# KGGR_wD_HK.net
KiCad netlist of a schematic drawn in EAGLE
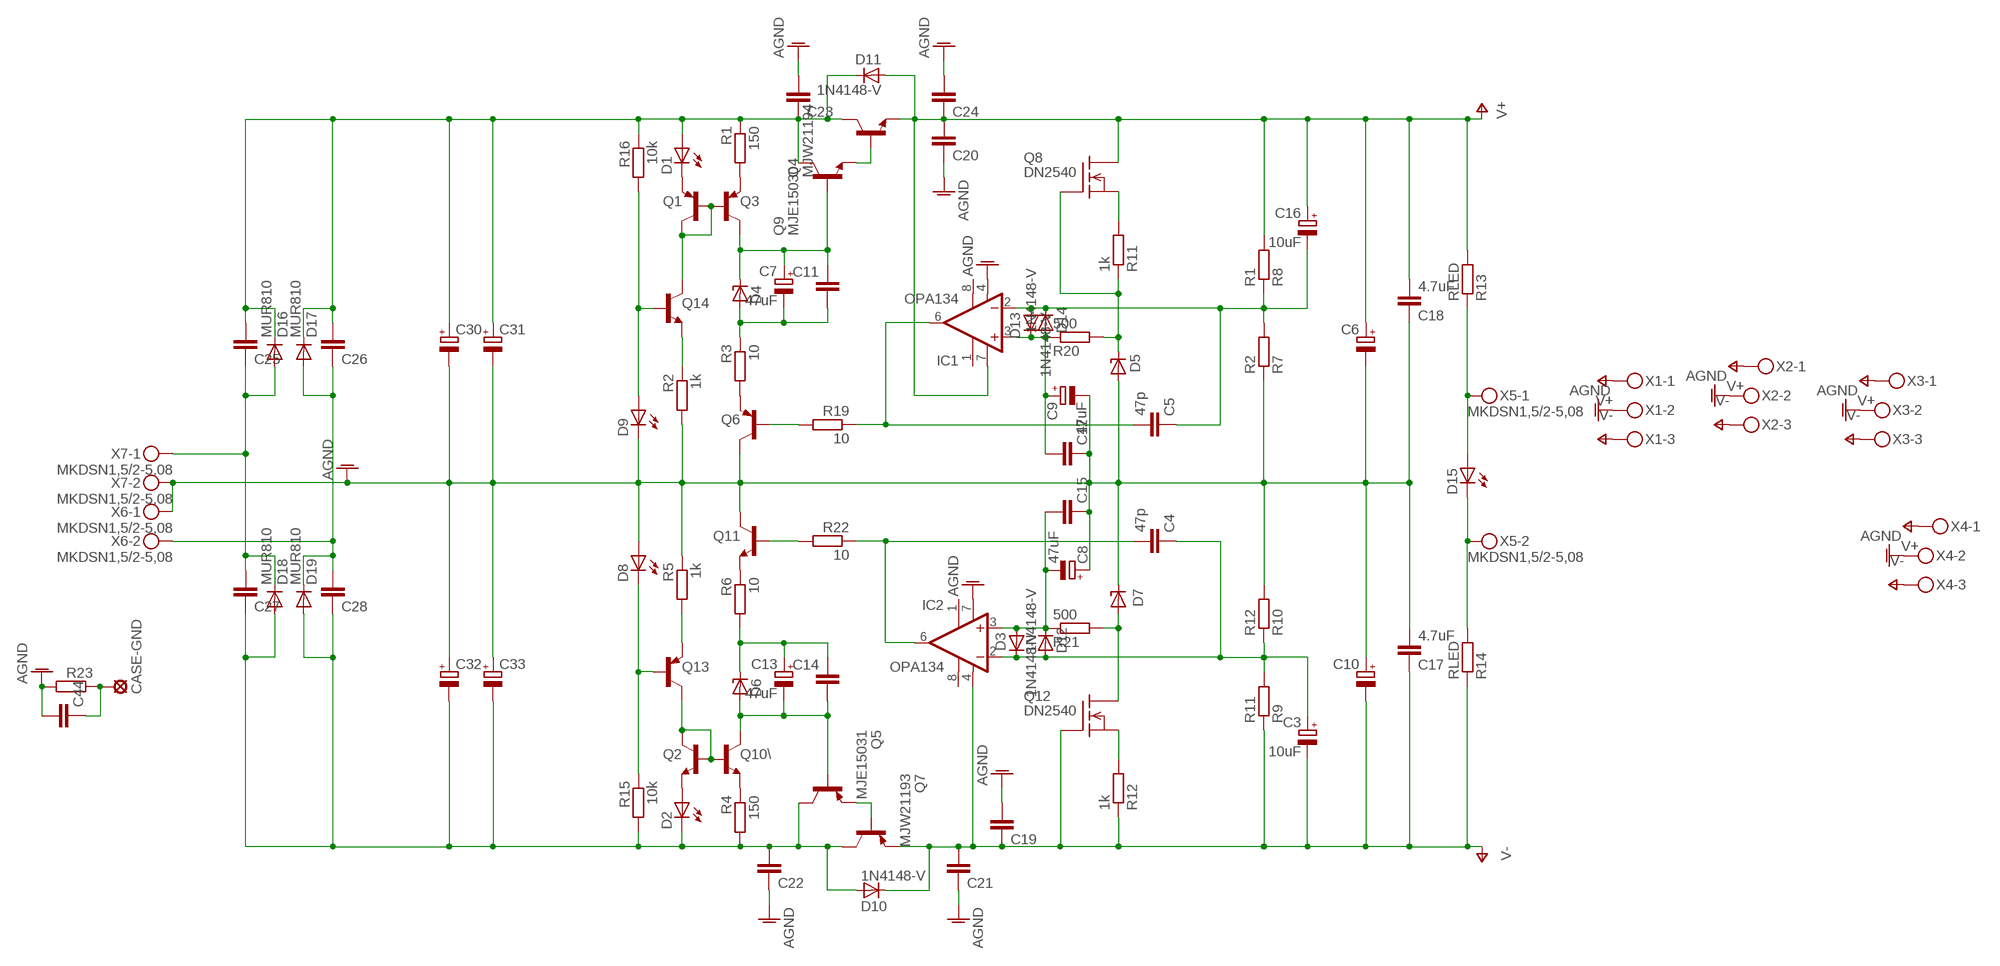
[diagram p0: schematic, sheet 1]
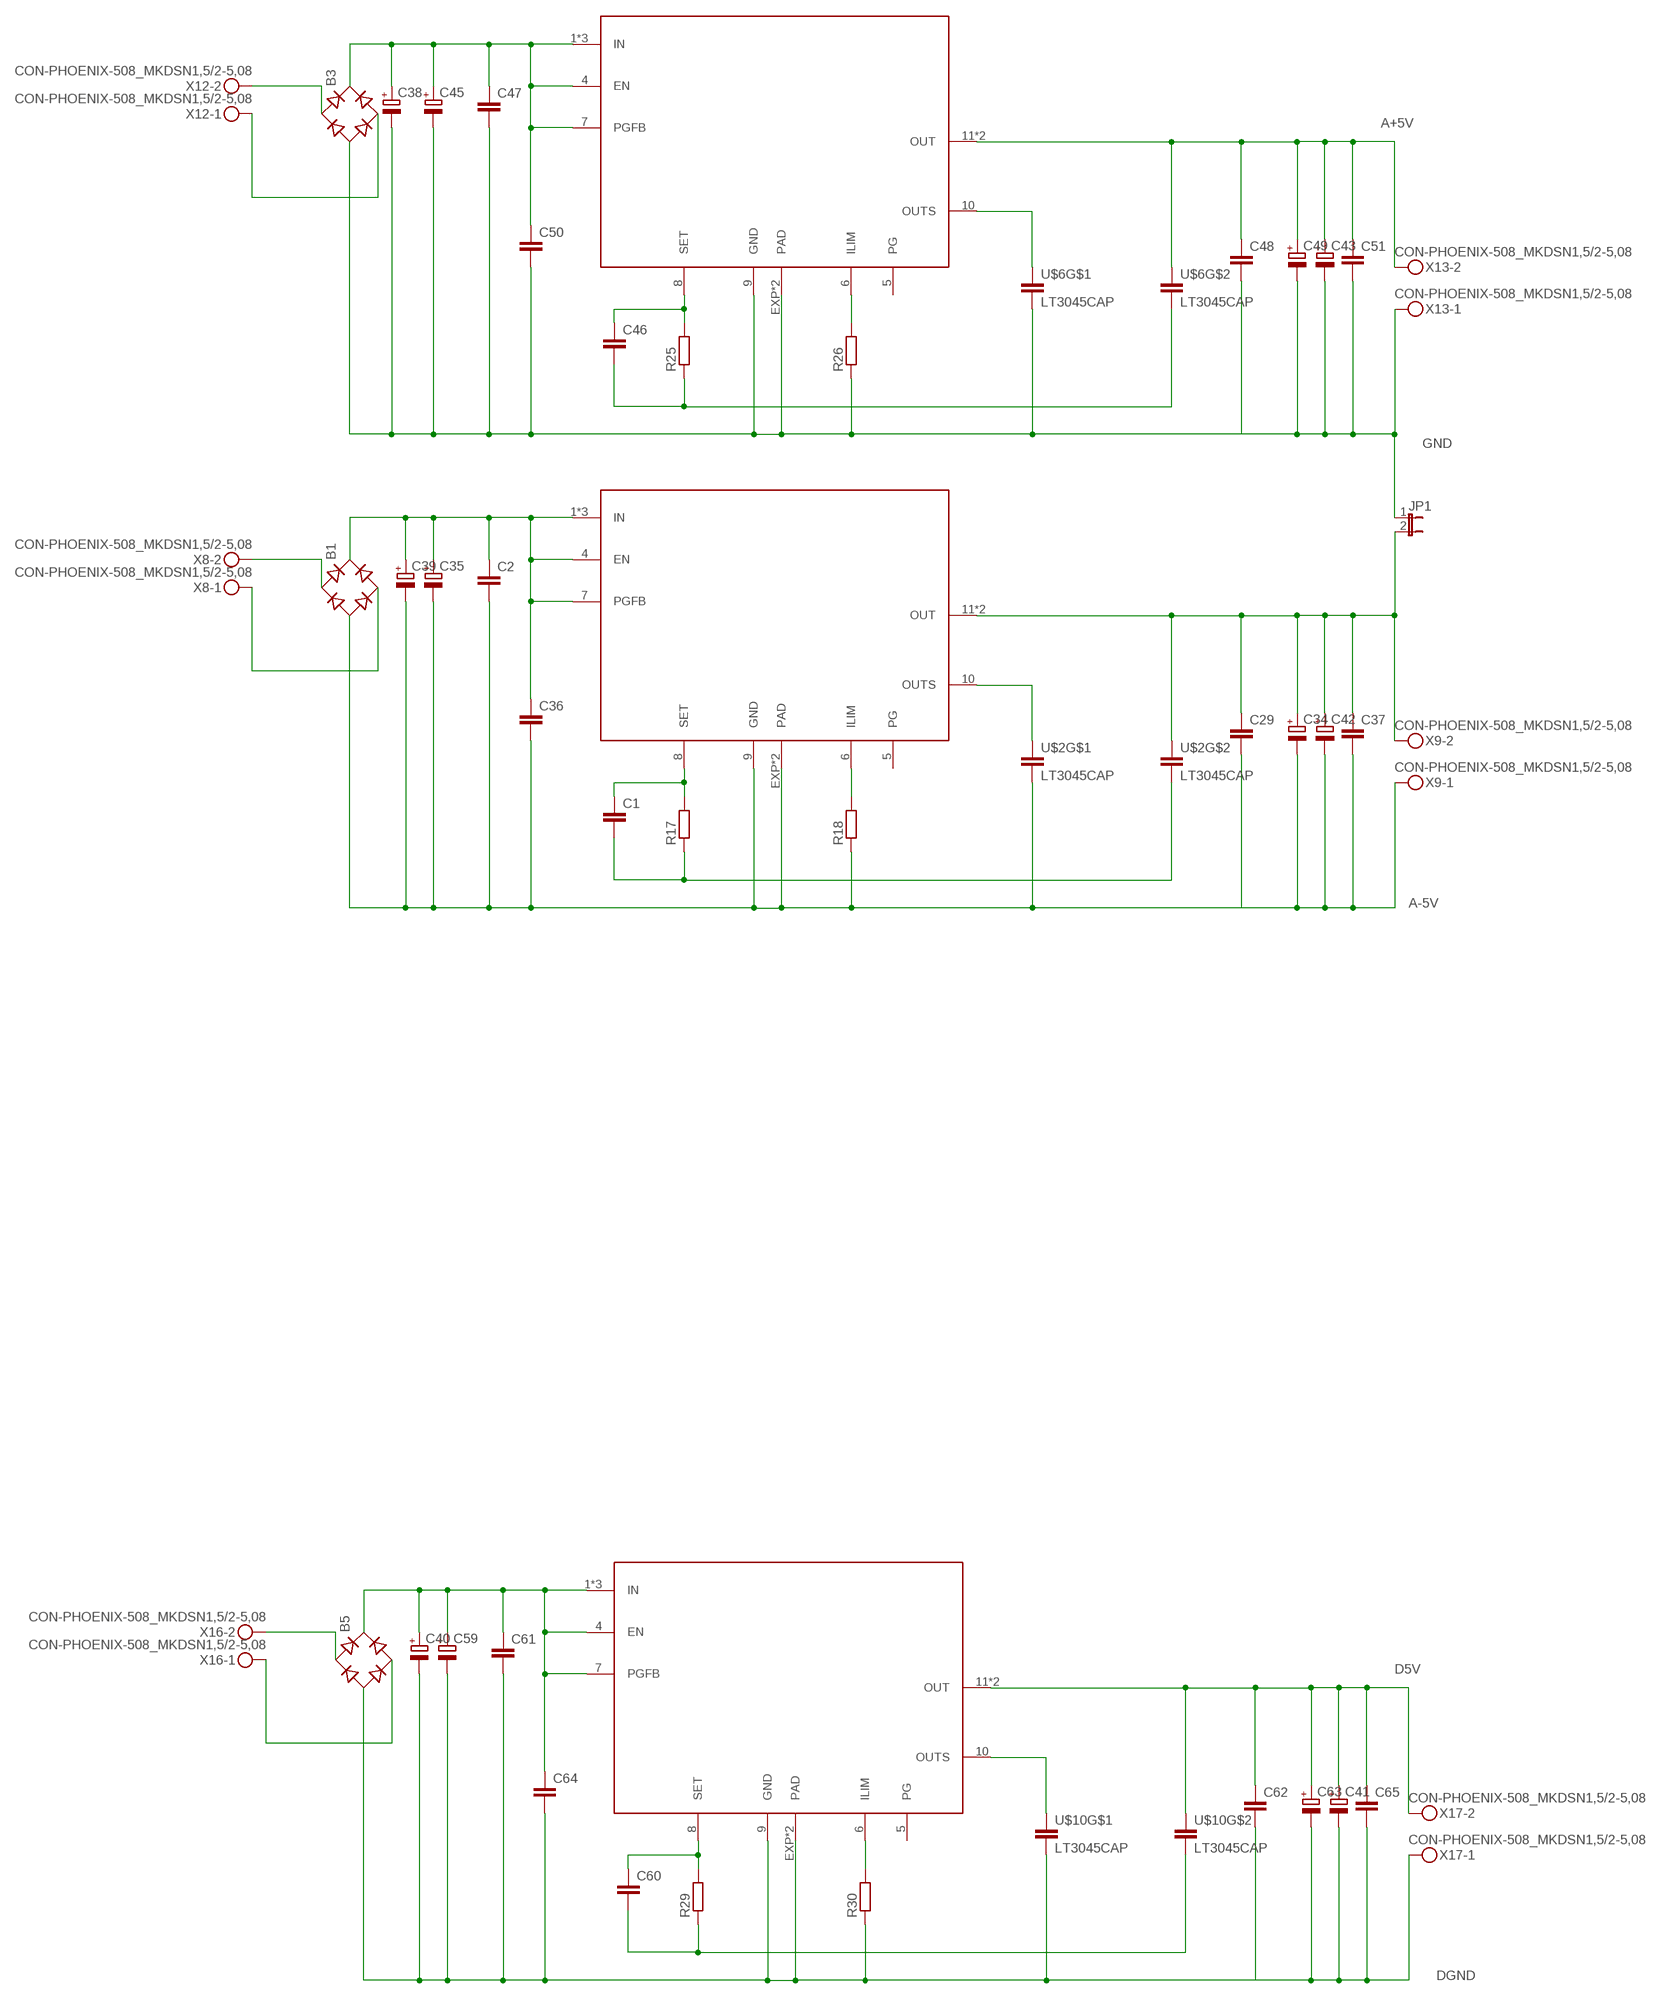
[diagram p1: schematic, sheet 2]

(export (version "E")
  (design (tool "Eeschema 10.0.6"))
  (components
    (comp (ref "C3")
      (value "10uF")
      (footprint "eagle-import:E5-8,5")
      (libsource (lib "eagle-import") (part "CPOL-EUE5-8.5"))
    )
    (comp (ref "C4")
      (value "47p")
      (footprint "eagle-import:C025_050-025X075")
      (libsource (lib "eagle-import") (part "C-EU025_050-025X075"))
    )
    (comp (ref "C5")
      (value "47p")
      (footprint "eagle-import:C025_050-025X075")
      (libsource (lib "eagle-import") (part "C-EU025_050-025X075"))
    )
    (comp (ref "C6")
      (value "CPOL-EUE7.5-18")
      (footprint "eagle-import:E7,5-18")
      (libsource (lib "eagle-import") (part "CPOL-EUE7.5-18"))
    )
    (comp (ref "C7")
      (value "47uF")
      (footprint "eagle-import:E5-8,5")
      (libsource (lib "eagle-import") (part "CPOL-EUE5-8.5"))
    )
    (comp (ref "C8")
      (value "47uF")
      (footprint "eagle-import:E5-8,5")
      (libsource (lib "eagle-import") (part "CPOL-EUE5-8.5"))
    )
    (comp (ref "C9")
      (value "47uF")
      (footprint "eagle-import:E5-8,5")
      (libsource (lib "eagle-import") (part "CPOL-EUE5-8.5"))
    )
    (comp (ref "C10")
      (value "CPOL-EUE7.5-18")
      (footprint "eagle-import:E7,5-18")
      (libsource (lib "eagle-import") (part "CPOL-EUE7.5-18"))
    )
    (comp (ref "C11")
      (value "C-EU050-035X075")
      (footprint "eagle-import:C050-035X075")
      (libsource (lib "eagle-import") (part "C-EU050-035X075"))
    )
    (comp (ref "C12")
      (value "C-EU050-035X075")
      (footprint "eagle-import:C050-035X075")
      (libsource (lib "eagle-import") (part "C-EU050-035X075"))
    )
    (comp (ref "C13")
      (value "47uF")
      (footprint "eagle-import:E5-8,5")
      (libsource (lib "eagle-import") (part "CPOL-EUE5-8.5"))
    )
    (comp (ref "C14")
      (value "C-EU050-035X075")
      (footprint "eagle-import:C050-035X075")
      (libsource (lib "eagle-import") (part "C-EU050-035X075"))
    )
    (comp (ref "C15")
      (value "C-EU050-035X075")
      (footprint "eagle-import:C050-035X075")
      (libsource (lib "eagle-import") (part "C-EU050-035X075"))
    )
    (comp (ref "C16")
      (value "10uF")
      (footprint "eagle-import:E5-8,5")
      (libsource (lib "eagle-import") (part "CPOL-EUE5-8.5"))
    )
    (comp (ref "C17")
      (value "4.7uF")
      (footprint "eagle-import:C050-075X075")
      (libsource (lib "eagle-import") (part "C-EU050-075X075"))
    )
    (comp (ref "C18")
      (value "4.7uF")
      (footprint "eagle-import:C050-075X075")
      (libsource (lib "eagle-import") (part "C-EU050-075X075"))
    )
    (comp (ref "C19")
      (value "C-EU050-035X075")
      (footprint "eagle-import:C050-035X075")
      (libsource (lib "eagle-import") (part "C-EU050-035X075"))
    )
    (comp (ref "C20")
      (value "C-EU050-035X075")
      (footprint "eagle-import:C050-035X075")
      (libsource (lib "eagle-import") (part "C-EU050-035X075"))
    )
    (comp (ref "C21")
      (value "C-EU050-035X075")
      (footprint "eagle-import:C050-035X075")
      (libsource (lib "eagle-import") (part "C-EU050-035X075"))
    )
    (comp (ref "C22")
      (value "C-EU050-075X075")
      (footprint "eagle-import:C050-075X075")
      (libsource (lib "eagle-import") (part "C-EU050-075X075"))
    )
    (comp (ref "C23")
      (value "C-EU050-075X075")
      (footprint "eagle-import:C050-075X075")
      (libsource (lib "eagle-import") (part "C-EU050-075X075"))
    )
    (comp (ref "C24")
      (value "C-EU050-035X075")
      (footprint "eagle-import:C050-035X075")
      (libsource (lib "eagle-import") (part "C-EU050-035X075"))
    )
    (comp (ref "C25")
      (value "C-EU050-035X075")
      (footprint "eagle-import:C050-035X075")
      (libsource (lib "eagle-import") (part "C-EU050-035X075"))
    )
    (comp (ref "C26")
      (value "C-EU050-035X075")
      (footprint "eagle-import:C050-035X075")
      (libsource (lib "eagle-import") (part "C-EU050-035X075"))
    )
    (comp (ref "C27")
      (value "C-EU050-035X075")
      (footprint "eagle-import:C050-035X075")
      (libsource (lib "eagle-import") (part "C-EU050-035X075"))
    )
    (comp (ref "C28")
      (value "C-EU050-035X075")
      (footprint "eagle-import:C050-035X075")
      (libsource (lib "eagle-import") (part "C-EU050-035X075"))
    )
    (comp (ref "C30")
      (value "CPOL-EUE10-35")
      (footprint "eagle-import:EB35D")
      (libsource (lib "eagle-import") (part "CPOL-EUE10-35"))
    )
    (comp (ref "C31")
      (value "CPOL-EUE10-35")
      (footprint "eagle-import:EB35D")
      (libsource (lib "eagle-import") (part "CPOL-EUE10-35"))
    )
    (comp (ref "C32")
      (value "CPOL-EUE10-35")
      (footprint "eagle-import:EB35D")
      (libsource (lib "eagle-import") (part "CPOL-EUE10-35"))
    )
    (comp (ref "C33")
      (value "CPOL-EUE10-35")
      (footprint "eagle-import:EB35D")
      (libsource (lib "eagle-import") (part "CPOL-EUE10-35"))
    )
    (comp (ref "C44")
      (value "C-EU075-052X106")
      (footprint "eagle-import:C075-052X106")
      (libsource (lib "eagle-import") (part "C-EU075-052X106"))
    )
    (comp (ref "CASE-GND")
      (value "SE14")
      (footprint "eagle-import:SE14")
      (libsource (lib "eagle-import") (part "SE14"))
    )
    (comp (ref "D1")
      (value "LED5MM")
      (footprint "eagle-import:LED5MM")
      (libsource (lib "eagle-import") (part "LED5MM"))
    )
    (comp (ref "D2")
      (value "LED5MM")
      (footprint "eagle-import:LED5MM")
      (libsource (lib "eagle-import") (part "LED5MM"))
    )
    (comp (ref "D3")
      (value "1N4148-V")
      (footprint "eagle-import:1N4148")
      (libsource (lib "eagle-import") (part "1N4148-V"))
    )
    (comp (ref "D4")
      (value "1N4728")
      (footprint "eagle-import:DO41Z10")
      (libsource (lib "eagle-import") (part "1N4728"))
    )
    (comp (ref "D5")
      (value "LT1021")
      (footprint "eagle-import:DIL08")
      (libsource (lib "eagle-import") (part "LT1021-V"))
    )
    (comp (ref "D6")
      (value "1N4728")
      (footprint "eagle-import:DO41Z10")
      (libsource (lib "eagle-import") (part "1N4728"))
    )
    (comp (ref "D7")
      (value "LT1021")
      (footprint "eagle-import:DIL08")
      (libsource (lib "eagle-import") (part "LT1021-V"))
    )
    (comp (ref "D8")
      (value "LED5MM")
      (footprint "eagle-import:LED5MM")
      (libsource (lib "eagle-import") (part "LED5MM"))
    )
    (comp (ref "D9")
      (value "LED5MM")
      (footprint "eagle-import:LED5MM")
      (libsource (lib "eagle-import") (part "LED5MM"))
    )
    (comp (ref "D10")
      (value "1N4148-V")
      (footprint "eagle-import:1N4148")
      (libsource (lib "eagle-import") (part "1N4148-V"))
    )
    (comp (ref "D11")
      (value "1N4148-V")
      (footprint "eagle-import:1N4148")
      (libsource (lib "eagle-import") (part "1N4148-V"))
    )
    (comp (ref "D12")
      (value "1N4148-V")
      (footprint "eagle-import:1N4148")
      (libsource (lib "eagle-import") (part "1N4148-V"))
    )
    (comp (ref "D13")
      (value "1N4148-V")
      (footprint "eagle-import:1N4148")
      (libsource (lib "eagle-import") (part "1N4148-V"))
    )
    (comp (ref "D14")
      (value "1N4148-V")
      (footprint "eagle-import:1N4148")
      (libsource (lib "eagle-import") (part "1N4148-V"))
    )
    (comp (ref "D15")
      (value "LED5MM")
      (footprint "eagle-import:LED5MM")
      (libsource (lib "eagle-import") (part "LED5MM"))
    )
    (comp (ref "D16")
      (value "MUR810")
      (footprint "eagle-import:TO220ACS")
      (libsource (lib "eagle-import") (part "MUR810"))
    )
    (comp (ref "D17")
      (value "MUR810")
      (footprint "eagle-import:TO220ACS")
      (libsource (lib "eagle-import") (part "MUR810"))
    )
    (comp (ref "D18")
      (value "MUR810")
      (footprint "eagle-import:TO220ACS")
      (libsource (lib "eagle-import") (part "MUR810"))
    )
    (comp (ref "D19")
      (value "MUR810")
      (footprint "eagle-import:TO220ACS")
      (libsource (lib "eagle-import") (part "MUR810"))
    )
    (comp (ref "IC1")
      (value "OPA134")
      (footprint "eagle-import:DIL08")
      (fields (field (name "MF") "TEXAS INSTRUMENTS") (field (name "MPN") "OPA134PA"))
      (libsource (lib "eagle-import") (part "OPA134P"))
    )
    (comp (ref "IC2")
      (value "OPA134")
      (footprint "eagle-import:DIL08")
      (fields (field (name "MF") "TEXAS INSTRUMENTS") (field (name "MPN") "OPA134PA"))
      (libsource (lib "eagle-import") (part "OPA134P"))
    )
    (comp (ref "Q1")
      (value "MPSA92-PNP-TO92-EBC")
      (footprint "eagle-import:TO92-EBC")
      (libsource (lib "eagle-import") (part "-PNP-TO92-EBCMPSA92"))
    )
    (comp (ref "Q2")
      (value "MPSA42-NPN-TO92-EBC")
      (footprint "eagle-import:TO92-EBC")
      (libsource (lib "eagle-import") (part "-NPN-TO92-EBCMPSA42"))
    )
    (comp (ref "Q3")
      (value "MPSA92-PNP-TO92-EBC")
      (footprint "eagle-import:TO92-EBC")
      (libsource (lib "eagle-import") (part "-PNP-TO92-EBCMPSA92"))
    )
    (comp (ref "Q4")
      (value "MJW21194")
      (footprint "eagle-import:TO-264")
      (libsource (lib "eagle-import") (part "MJL4281"))
    )
    (comp (ref "Q5")
      (value "MJE15031")
      (footprint "eagle-import:TO220KG")
      (libsource (lib "eagle-import") (part "MJE15031"))
    )
    (comp (ref "Q6")
      (value "MPSA92-PNP-TO92-EBC")
      (footprint "eagle-import:TO92-EBC")
      (libsource (lib "eagle-import") (part "-PNP-TO92-EBCMPSA92"))
    )
    (comp (ref "Q7")
      (value "MJW21193")
      (footprint "eagle-import:TO-264")
      (libsource (lib "eagle-import") (part "MJL4302"))
    )
    (comp (ref "Q8")
      (value "DN2540")
      (footprint "eagle-import:TO92-")
      (libsource (lib "eagle-import") (part "2N7000"))
    )
    (comp (ref "Q9")
      (value "MJE15030")
      (footprint "eagle-import:TO220KG")
      (libsource (lib "eagle-import") (part "MJE15030"))
    )
    (comp (ref "Q10\\")
      (value "MPSA42-NPN-TO92-EBC")
      (footprint "eagle-import:TO92-EBC")
      (libsource (lib "eagle-import") (part "-NPN-TO92-EBCMPSA42"))
    )
    (comp (ref "Q11")
      (value "MPSA42-NPN-TO92-EBC")
      (footprint "eagle-import:TO92-EBC")
      (libsource (lib "eagle-import") (part "-NPN-TO92-EBCMPSA42"))
    )
    (comp (ref "Q12")
      (value "DN2540")
      (footprint "eagle-import:TO92-")
      (libsource (lib "eagle-import") (part "2N7000"))
    )
    (comp (ref "Q13")
      (value "MPSA92-PNP-TO92-EBC")
      (footprint "eagle-import:TO92-EBC")
      (libsource (lib "eagle-import") (part "-PNP-TO92-EBCMPSA92"))
    )
    (comp (ref "Q14")
      (value "MPSA42-NPN-TO92-EBC")
      (footprint "eagle-import:TO92-EBC")
      (libsource (lib "eagle-import") (part "-NPN-TO92-EBCMPSA42"))
    )
    (comp (ref "R1")
      (value "150")
      (footprint "eagle-import:0309_12")
      (libsource (lib "eagle-import") (part "R-EU_0309/12"))
    )
    (comp (ref "R2")
      (value "1k")
      (footprint "eagle-import:0309_12")
      (libsource (lib "eagle-import") (part "R-EU_0309/12"))
    )
    (comp (ref "R3")
      (value "10")
      (footprint "eagle-import:0309_12")
      (libsource (lib "eagle-import") (part "R-EU_0309/12"))
    )
    (comp (ref "R4")
      (value "150")
      (footprint "eagle-import:0309_12")
      (libsource (lib "eagle-import") (part "R-EU_0309/12"))
    )
    (comp (ref "R5")
      (value "1k")
      (footprint "eagle-import:0309_12")
      (libsource (lib "eagle-import") (part "R-EU_0309/12"))
    )
    (comp (ref "R6")
      (value "10")
      (footprint "eagle-import:0309_12")
      (libsource (lib "eagle-import") (part "R-EU_0309/12"))
    )
    (comp (ref "R7")
      (value "R2")
      (footprint "eagle-import:0309_12")
      (libsource (lib "eagle-import") (part "R-EU_0309/12"))
    )
    (comp (ref "R8")
      (value "R1")
      (footprint "eagle-import:0309_12")
      (libsource (lib "eagle-import") (part "R-EU_0309/12"))
    )
    (comp (ref "R9")
      (value "R11")
      (footprint "eagle-import:0309_12")
      (libsource (lib "eagle-import") (part "R-EU_0309/12"))
    )
    (comp (ref "R10")
      (value "R12")
      (footprint "eagle-import:0309_12")
      (libsource (lib "eagle-import") (part "R-EU_0309/12"))
    )
    (comp (ref "R11")
      (value "1k")
      (footprint "eagle-import:0309_12")
      (libsource (lib "eagle-import") (part "R-EU_0309/12"))
    )
    (comp (ref "R12")
      (value "1k")
      (footprint "eagle-import:0309_12")
      (libsource (lib "eagle-import") (part "R-EU_0309/12"))
    )
    (comp (ref "R13")
      (value "RLED")
      (footprint "eagle-import:0309_12")
      (libsource (lib "eagle-import") (part "R-EU_0309/12"))
    )
    (comp (ref "R14")
      (value "RLED")
      (footprint "eagle-import:0309_12")
      (libsource (lib "eagle-import") (part "R-EU_0309/12"))
    )
    (comp (ref "R15")
      (value "10k")
      (footprint "eagle-import:0309_12")
      (libsource (lib "eagle-import") (part "R-EU_0309/12"))
    )
    (comp (ref "R16")
      (value "10k")
      (footprint "eagle-import:0309_12")
      (libsource (lib "eagle-import") (part "R-EU_0309/12"))
    )
    (comp (ref "R19")
      (value "10")
      (footprint "eagle-import:0309_12")
      (libsource (lib "eagle-import") (part "R-EU_0309/12"))
    )
    (comp (ref "R20")
      (value "500")
      (footprint "eagle-import:0309_12")
      (libsource (lib "eagle-import") (part "R-EU_0309/12"))
    )
    (comp (ref "R21")
      (value "500")
      (footprint "eagle-import:0309_12")
      (libsource (lib "eagle-import") (part "R-EU_0309/12"))
    )
    (comp (ref "R22")
      (value "10")
      (footprint "eagle-import:0309_12")
      (libsource (lib "eagle-import") (part "R-EU_0309/12"))
    )
    (comp (ref "R23")
      (value "R-EU_0411/12")
      (footprint "eagle-import:0411_12")
      (libsource (lib "eagle-import") (part "R-EU_0411/12"))
    )
    (comp (ref "X1")
      (value "MKDSN1,5/3-5,08")
      (footprint "eagle-import:MKDSN1,5_3-5,08")
      (libsource (lib "eagle-import") (part "MKDSN1,5/3-5,08"))
    )
    (comp (ref "X2")
      (value "MKDSN1,5/3-5,08")
      (footprint "eagle-import:MKDSN1,5_3-5,08")
      (libsource (lib "eagle-import") (part "MKDSN1,5/3-5,08"))
    )
    (comp (ref "X3")
      (value "MKDSN1,5/3-5,08")
      (footprint "eagle-import:MKDSN1,5_3-5,08")
      (libsource (lib "eagle-import") (part "MKDSN1,5/3-5,08"))
    )
    (comp (ref "X4")
      (value "MKDSN1,5/3-5,08")
      (footprint "eagle-import:MKDSN1,5_3-5,08")
      (libsource (lib "eagle-import") (part "MKDSN1,5/3-5,08"))
    )
    (comp (ref "X5")
      (value "MKDSN1,5/2-5,08")
      (footprint "eagle-import:MKDSN1,5_2-5,08")
      (libsource (lib "eagle-import") (part "MKDSN1,5/2-5,08"))
    )
    (comp (ref "X6")
      (value "MKDSN1,5/2-5,08")
      (footprint "eagle-import:MKDSN1,5_2-5,08")
      (libsource (lib "eagle-import") (part "MKDSN1,5/2-5,08"))
    )
    (comp (ref "X7")
      (value "MKDSN1,5/2-5,08")
      (footprint "eagle-import:MKDSN1,5_2-5,08")
      (libsource (lib "eagle-import") (part "MKDSN1,5/2-5,08"))
    )
    (comp (ref "B1")
      (value "RB1A")
      (footprint "eagle-import:RB1A")
      (libsource (lib "eagle-import") (part "RB1A"))
    )
    (comp (ref "B3")
      (value "RB1A")
      (footprint "eagle-import:RB1A")
      (libsource (lib "eagle-import") (part "RB1A"))
    )
    (comp (ref "B5")
      (value "RB1A")
      (footprint "eagle-import:RB1A")
      (libsource (lib "eagle-import") (part "RB1A"))
    )
    (comp (ref "C1")
      (value "C-EUC1206")
      (footprint "eagle-import:C1206")
      (libsource (lib "eagle-import") (part "C-EUC1206"))
    )
    (comp (ref "C2")
      (value "C-EU050-050X075")
      (footprint "eagle-import:C050-050X075")
      (libsource (lib "eagle-import") (part "C-EU050-050X075"))
    )
    (comp (ref "C29")
      (value "C-EU050-050X075")
      (footprint "eagle-import:C050-050X075")
      (libsource (lib "eagle-import") (part "C-EU050-050X075"))
    )
    (comp (ref "C34")
      (value "CPOL-EUE5-10.5")
      (footprint "eagle-import:E5-10,5")
      (libsource (lib "eagle-import") (part "CPOL-EUE5-10.5"))
    )
    (comp (ref "C35")
      (value "CPOL-EUE10-25")
      (footprint "eagle-import:EB25D")
      (libsource (lib "eagle-import") (part "CPOL-EUE10-25"))
    )
    (comp (ref "C36")
      (value "C-EUC1206")
      (footprint "eagle-import:C1206")
      (libsource (lib "eagle-import") (part "C-EUC1206"))
    )
    (comp (ref "C37")
      (value "C-EUC1206")
      (footprint "eagle-import:C1206")
      (libsource (lib "eagle-import") (part "C-EUC1206"))
    )
    (comp (ref "C38")
      (value "CPOL-EUSP-CAP-CX")
      (footprint "eagle-import:SP-CAP-CX")
      (libsource (lib "eagle-import") (part "CPOL-EUSP-CAP-CX"))
    )
    (comp (ref "C39")
      (value "CPOL-EUSP-CAP-CX")
      (footprint "eagle-import:SP-CAP-CX")
      (libsource (lib "eagle-import") (part "CPOL-EUSP-CAP-CX"))
    )
    (comp (ref "C40")
      (value "CPOL-EUSP-CAP-CX")
      (footprint "eagle-import:SP-CAP-CX")
      (libsource (lib "eagle-import") (part "CPOL-EUSP-CAP-CX"))
    )
    (comp (ref "C41")
      (value "CPOL-EUSP-CAP-CX")
      (footprint "eagle-import:SP-CAP-CX")
      (libsource (lib "eagle-import") (part "CPOL-EUSP-CAP-CX"))
    )
    (comp (ref "C42")
      (value "CPOL-EUSP-CAP-CX")
      (footprint "eagle-import:SP-CAP-CX")
      (libsource (lib "eagle-import") (part "CPOL-EUSP-CAP-CX"))
    )
    (comp (ref "C43")
      (value "CPOL-EUSP-CAP-CX")
      (footprint "eagle-import:SP-CAP-CX")
      (libsource (lib "eagle-import") (part "CPOL-EUSP-CAP-CX"))
    )
    (comp (ref "C45")
      (value "CPOL-EUE10-25")
      (footprint "eagle-import:EB25D")
      (libsource (lib "eagle-import") (part "CPOL-EUE10-25"))
    )
    (comp (ref "C46")
      (value "C-EUC1206")
      (footprint "eagle-import:C1206")
      (libsource (lib "eagle-import") (part "C-EUC1206"))
    )
    (comp (ref "C47")
      (value "C-EU050-050X075")
      (footprint "eagle-import:C050-050X075")
      (libsource (lib "eagle-import") (part "C-EU050-050X075"))
    )
    (comp (ref "C48")
      (value "C-EU050-050X075")
      (footprint "eagle-import:C050-050X075")
      (libsource (lib "eagle-import") (part "C-EU050-050X075"))
    )
    (comp (ref "C49")
      (value "CPOL-EUE5-10.5")
      (footprint "eagle-import:E5-10,5")
      (libsource (lib "eagle-import") (part "CPOL-EUE5-10.5"))
    )
    (comp (ref "C50")
      (value "C-EUC1206")
      (footprint "eagle-import:C1206")
      (libsource (lib "eagle-import") (part "C-EUC1206"))
    )
    (comp (ref "C51")
      (value "C-EUC1206")
      (footprint "eagle-import:C1206")
      (libsource (lib "eagle-import") (part "C-EUC1206"))
    )
    (comp (ref "C59")
      (value "CPOL-EUE10-25")
      (footprint "eagle-import:EB25D")
      (libsource (lib "eagle-import") (part "CPOL-EUE10-25"))
    )
    (comp (ref "C60")
      (value "C-EUC1206")
      (footprint "eagle-import:C1206")
      (libsource (lib "eagle-import") (part "C-EUC1206"))
    )
    (comp (ref "C61")
      (value "C-EU050-050X075")
      (footprint "eagle-import:C050-050X075")
      (libsource (lib "eagle-import") (part "C-EU050-050X075"))
    )
    (comp (ref "C62")
      (value "C-EU050-050X075")
      (footprint "eagle-import:C050-050X075")
      (libsource (lib "eagle-import") (part "C-EU050-050X075"))
    )
    (comp (ref "C63")
      (value "CPOL-EUE5-10.5")
      (footprint "eagle-import:E5-10,5")
      (libsource (lib "eagle-import") (part "CPOL-EUE5-10.5"))
    )
    (comp (ref "C64")
      (value "C-EUC1206")
      (footprint "eagle-import:C1206")
      (libsource (lib "eagle-import") (part "C-EUC1206"))
    )
    (comp (ref "C65")
      (value "C-EUC1206")
      (footprint "eagle-import:C1206")
      (libsource (lib "eagle-import") (part "C-EUC1206"))
    )
    (comp (ref "JP1")
      (value "JP1E")
      (footprint "eagle-import:JP1")
      (libsource (lib "eagle-import") (part "JP1E"))
    )
    (comp (ref "R17")
      (value "R-EU_MELF0204R")
      (footprint "eagle-import:MINI_MELF-0204R")
      (libsource (lib "eagle-import") (part "R-EU_MELF0204R"))
    )
    (comp (ref "R18")
      (value "R-EU_MELF0204R")
      (footprint "eagle-import:MINI_MELF-0204R")
      (libsource (lib "eagle-import") (part "R-EU_MELF0204R"))
    )
    (comp (ref "R25")
      (value "R-EU_MELF0204R")
      (footprint "eagle-import:MINI_MELF-0204R")
      (libsource (lib "eagle-import") (part "R-EU_MELF0204R"))
    )
    (comp (ref "R26")
      (value "R-EU_MELF0204R")
      (footprint "eagle-import:MINI_MELF-0204R")
      (libsource (lib "eagle-import") (part "R-EU_MELF0204R"))
    )
    (comp (ref "R29")
      (value "R-EU_MELF0204R")
      (footprint "eagle-import:MINI_MELF-0204R")
      (libsource (lib "eagle-import") (part "R-EU_MELF0204R"))
    )
    (comp (ref "R30")
      (value "R-EU_MELF0204R")
      (footprint "eagle-import:MINI_MELF-0204R")
      (libsource (lib "eagle-import") (part "R-EU_MELF0204R"))
    )
    (comp (ref "U$1")
      (value "LT3045")
      (footprint "eagle-import:MSOP12")
      (libsource (lib "eagle-import") (part "LT3045"))
    )
    (comp (ref "U$2")
      (value "LT3045CAP")
      (footprint "eagle-import:LT3045CAP")
      (libsource (lib "eagle-import") (part "LT3045CAP"))
    )
    (comp (ref "U$5")
      (value "LT3045")
      (footprint "eagle-import:MSOP12")
      (libsource (lib "eagle-import") (part "LT3045"))
    )
    (comp (ref "U$6")
      (value "LT3045CAP")
      (footprint "eagle-import:LT3045CAP")
      (libsource (lib "eagle-import") (part "LT3045CAP"))
    )
    (comp (ref "U$9")
      (value "LT3045")
      (footprint "eagle-import:MSOP12")
      (libsource (lib "eagle-import") (part "LT3045"))
    )
    (comp (ref "U$10")
      (value "LT3045CAP")
      (footprint "eagle-import:LT3045CAP")
      (libsource (lib "eagle-import") (part "LT3045CAP"))
    )
    (comp (ref "X8")
      (value "CON-PHOENIX-508_MKDSN1,5/2-5,08")
      (footprint "eagle-import:CON-PHOENIX-508_MKDSN1,5_2-5,08")
      (libsource (lib "eagle-import") (part "CON-PHOENIX-508_MKDSN1,5/2-5,08"))
    )
    (comp (ref "X9")
      (value "CON-PHOENIX-508_MKDSN1,5/2-5,08")
      (footprint "eagle-import:CON-PHOENIX-508_MKDSN1,5_2-5,08")
      (libsource (lib "eagle-import") (part "CON-PHOENIX-508_MKDSN1,5/2-5,08"))
    )
    (comp (ref "X12")
      (value "CON-PHOENIX-508_MKDSN1,5/2-5,08")
      (footprint "eagle-import:CON-PHOENIX-508_MKDSN1,5_2-5,08")
      (libsource (lib "eagle-import") (part "CON-PHOENIX-508_MKDSN1,5/2-5,08"))
    )
    (comp (ref "X13")
      (value "CON-PHOENIX-508_MKDSN1,5/2-5,08")
      (footprint "eagle-import:CON-PHOENIX-508_MKDSN1,5_2-5,08")
      (libsource (lib "eagle-import") (part "CON-PHOENIX-508_MKDSN1,5/2-5,08"))
    )
    (comp (ref "X16")
      (value "CON-PHOENIX-508_MKDSN1,5/2-5,08")
      (footprint "eagle-import:CON-PHOENIX-508_MKDSN1,5_2-5,08")
      (libsource (lib "eagle-import") (part "CON-PHOENIX-508_MKDSN1,5/2-5,08"))
    )
    (comp (ref "X17")
      (value "CON-PHOENIX-508_MKDSN1,5/2-5,08")
      (footprint "eagle-import:CON-PHOENIX-508_MKDSN1,5_2-5,08")
      (libsource (lib "eagle-import") (part "CON-PHOENIX-508_MKDSN1,5/2-5,08"))
    )
  )
  (nets
    (net (code "1") (name "A+5V") (class "Default")
      (node (ref "C43") (pin "+") (pinfunction "+_+") (pintype "passive"))
      (node (ref "C48") (pin "1") (pinfunction "1_1") (pintype "passive"))
      (node (ref "C49") (pin "+") (pinfunction "+_+") (pintype "passive"))
      (node (ref "C51") (pin "1") (pinfunction "1_1") (pintype "passive"))
      (node (ref "U$5") (pin "11") (pinfunction "OUT_11") (pintype "bidirectional"))
      (node (ref "U$5") (pin "12") (pinfunction "OUT_12") (pintype "bidirectional"))
      (node (ref "U$6") (pin "4") (pinfunction "1_4") (pintype "passive"))
      (node (ref "X13") (pin "2") (pinfunction "KL_2") (pintype "passive"))
    )
    (net (code "2") (name "A-5V") (class "Default")
      (node (ref "B1") (pin "-") (pinfunction "-_-") (pintype "passive"))
      (node (ref "C2") (pin "2") (pinfunction "2_2") (pintype "passive"))
      (node (ref "C29") (pin "2") (pinfunction "2_2") (pintype "passive"))
      (node (ref "C34") (pin "-") (pinfunction "-_-") (pintype "passive"))
      (node (ref "C35") (pin "-") (pinfunction "-_-") (pintype "passive"))
      (node (ref "C36") (pin "2") (pinfunction "2_2") (pintype "passive"))
      (node (ref "C37") (pin "2") (pinfunction "2_2") (pintype "passive"))
      (node (ref "C39") (pin "-") (pinfunction "-_-") (pintype "passive"))
      (node (ref "C42") (pin "-") (pinfunction "-_-") (pintype "passive"))
      (node (ref "R18") (pin "1") (pinfunction "1_1") (pintype "passive"))
      (node (ref "U$1") (pin "9") (pinfunction "GND_9") (pintype "bidirectional"))
      (node (ref "U$1") (pin "EXP") (pinfunction "PAD_EXP") (pintype "bidirectional"))
      (node (ref "U$1") (pin "EXP1") (pinfunction "PAD_EXP1") (pintype "bidirectional"))
      (node (ref "U$2") (pin "5") (pinfunction "2_5") (pintype "passive"))
      (node (ref "X9") (pin "1") (pinfunction "KL_1") (pintype "passive"))
    )
    (net (code "3") (name "AGND") (class "Default")
      (node (ref "C10") (pin "+") (pinfunction "+_+") (pintype "passive"))
      (node (ref "C12") (pin "1") (pinfunction "1_1") (pintype "passive"))
      (node (ref "C15") (pin "1") (pinfunction "1_1") (pintype "passive"))
      (node (ref "C17") (pin "2") (pinfunction "2_2") (pintype "passive"))
      (node (ref "C18") (pin "1") (pinfunction "1_1") (pintype "passive"))
      (node (ref "C19") (pin "2") (pinfunction "2_2") (pintype "passive"))
      (node (ref "C20") (pin "1") (pinfunction "1_1") (pintype "passive"))
      (node (ref "C21") (pin "1") (pinfunction "1_1") (pintype "passive"))
      (node (ref "C22") (pin "1") (pinfunction "1_1") (pintype "passive"))
      (node (ref "C23") (pin "2") (pinfunction "2_2") (pintype "passive"))
      (node (ref "C24") (pin "2") (pinfunction "2_2") (pintype "passive"))
      (node (ref "C30") (pin "-") (pinfunction "-_-") (pintype "passive"))
      (node (ref "C31") (pin "-") (pinfunction "-_-") (pintype "passive"))
      (node (ref "C32") (pin "+") (pinfunction "+_+") (pintype "passive"))
      (node (ref "C33") (pin "+") (pinfunction "+_+") (pintype "passive"))
      (node (ref "C44") (pin "2") (pinfunction "2_2") (pintype "passive"))
      (node (ref "C6") (pin "-") (pinfunction "-_-") (pintype "passive"))
      (node (ref "C8") (pin "+") (pinfunction "+_+") (pintype "passive"))
      (node (ref "C9") (pin "-") (pinfunction "-_-") (pintype "passive"))
      (node (ref "D5") (pin "4") (pinfunction "GND_4") (pintype "passive"))
      (node (ref "D7") (pin "6") (pinfunction "OUT_6") (pintype "passive"))
      (node (ref "D8") (pin "A") (pinfunction "A_A") (pintype "passive"))
      (node (ref "D9") (pin "K") (pinfunction "C_K") (pintype "passive"))
      (node (ref "IC1") (pin "4") (pinfunction "V-_4") (pintype "power_in"))
      (node (ref "IC2") (pin "7") (pinfunction "V+_7") (pintype "power_in"))
      (node (ref "Q11") (pin "C") (pinfunction "C_C") (pintype "passive"))
      (node (ref "Q6") (pin "C") (pinfunction "C_C") (pintype "passive"))
      (node (ref "R10") (pin "2") (pinfunction "2_2") (pintype "passive"))
      (node (ref "R2") (pin "2") (pinfunction "2_2") (pintype "passive"))
      (node (ref "R23") (pin "2") (pinfunction "2_2") (pintype "passive"))
      (node (ref "R5") (pin "1") (pinfunction "1_1") (pintype "passive"))
      (node (ref "R7") (pin "1") (pinfunction "1_1") (pintype "passive"))
      (node (ref "X1") (pin "2") (pinfunction "KL_2") (pintype "passive"))
      (node (ref "X2") (pin "2") (pinfunction "KL_2") (pintype "passive"))
      (node (ref "X3") (pin "2") (pinfunction "KL_2") (pintype "passive"))
      (node (ref "X4") (pin "2") (pinfunction "KL_2") (pintype "passive"))
      (node (ref "X6") (pin "1") (pinfunction "KL_1") (pintype "passive"))
      (node (ref "X7") (pin "2") (pinfunction "KL_2") (pintype "passive"))
    )
    (net (code "4") (name "D5V") (class "Default")
      (node (ref "C41") (pin "+") (pinfunction "+_+") (pintype "passive"))
      (node (ref "C62") (pin "1") (pinfunction "1_1") (pintype "passive"))
      (node (ref "C63") (pin "+") (pinfunction "+_+") (pintype "passive"))
      (node (ref "C65") (pin "1") (pinfunction "1_1") (pintype "passive"))
      (node (ref "U$10") (pin "4") (pinfunction "1_4") (pintype "passive"))
      (node (ref "U$9") (pin "11") (pinfunction "OUT_11") (pintype "bidirectional"))
      (node (ref "U$9") (pin "12") (pinfunction "OUT_12") (pintype "bidirectional"))
      (node (ref "X17") (pin "2") (pinfunction "KL_2") (pintype "passive"))
    )
    (net (code "5") (name "DGND") (class "Default")
      (node (ref "B5") (pin "-") (pinfunction "-_-") (pintype "passive"))
      (node (ref "C40") (pin "-") (pinfunction "-_-") (pintype "passive"))
      (node (ref "C41") (pin "-") (pinfunction "-_-") (pintype "passive"))
      (node (ref "C59") (pin "-") (pinfunction "-_-") (pintype "passive"))
      (node (ref "C61") (pin "2") (pinfunction "2_2") (pintype "passive"))
      (node (ref "C62") (pin "2") (pinfunction "2_2") (pintype "passive"))
      (node (ref "C63") (pin "-") (pinfunction "-_-") (pintype "passive"))
      (node (ref "C64") (pin "2") (pinfunction "2_2") (pintype "passive"))
      (node (ref "C65") (pin "2") (pinfunction "2_2") (pintype "passive"))
      (node (ref "R30") (pin "1") (pinfunction "1_1") (pintype "passive"))
      (node (ref "U$10") (pin "5") (pinfunction "2_5") (pintype "passive"))
      (node (ref "U$9") (pin "9") (pinfunction "GND_9") (pintype "bidirectional"))
      (node (ref "U$9") (pin "EXP") (pinfunction "PAD_EXP") (pintype "bidirectional"))
      (node (ref "U$9") (pin "EXP1") (pinfunction "PAD_EXP1") (pintype "bidirectional"))
      (node (ref "X17") (pin "1") (pinfunction "KL_1") (pintype "passive"))
    )
    (net (code "6") (name "GND") (class "Default")
      (node (ref "B3") (pin "-") (pinfunction "-_-") (pintype "passive"))
      (node (ref "C38") (pin "-") (pinfunction "-_-") (pintype "passive"))
      (node (ref "C43") (pin "-") (pinfunction "-_-") (pintype "passive"))
      (node (ref "C45") (pin "-") (pinfunction "-_-") (pintype "passive"))
      (node (ref "C47") (pin "2") (pinfunction "2_2") (pintype "passive"))
      (node (ref "C48") (pin "2") (pinfunction "2_2") (pintype "passive"))
      (node (ref "C49") (pin "-") (pinfunction "-_-") (pintype "passive"))
      (node (ref "C50") (pin "2") (pinfunction "2_2") (pintype "passive"))
      (node (ref "C51") (pin "2") (pinfunction "2_2") (pintype "passive"))
      (node (ref "JP1") (pin "1") (pinfunction "1_1") (pintype "passive"))
      (node (ref "R26") (pin "1") (pinfunction "1_1") (pintype "passive"))
      (node (ref "U$5") (pin "9") (pinfunction "GND_9") (pintype "bidirectional"))
      (node (ref "U$5") (pin "EXP") (pinfunction "PAD_EXP") (pintype "bidirectional"))
      (node (ref "U$5") (pin "EXP1") (pinfunction "PAD_EXP1") (pintype "bidirectional"))
      (node (ref "U$6") (pin "5") (pinfunction "2_5") (pintype "passive"))
      (node (ref "X13") (pin "1") (pinfunction "KL_1") (pintype "passive"))
    )
    (net (code "7") (name "Net-(C11-Pad2)") (class "Default")
      (node (ref "C11") (pin "2") (pinfunction "2_2") (pintype "passive"))
      (node (ref "C7") (pin "-") (pinfunction "-_-") (pintype "passive"))
      (node (ref "D4") (pin "A") (pinfunction "A_A") (pintype "passive"))
      (node (ref "R3") (pin "1") (pinfunction "1_1") (pintype "passive"))
    )
    (net (code "8") (name "Net-(C13-Pad+)") (class "Default")
      (node (ref "C13") (pin "+") (pinfunction "+_+") (pintype "passive"))
      (node (ref "C14") (pin "1") (pinfunction "1_1") (pintype "passive"))
      (node (ref "D6") (pin "C") (pinfunction "C_C") (pintype "passive"))
      (node (ref "R6") (pin "2") (pinfunction "2_2") (pintype "passive"))
    )
    (net (code "9") (name "Net-(C44-Pad1)") (class "Default")
      (node (ref "C44") (pin "1") (pinfunction "1_1") (pintype "passive"))
      (node (ref "CASE-GND") (pin "MP") (pinfunction "MP_MP") (pintype "passive"))
      (node (ref "R23") (pin "1") (pinfunction "1_1") (pintype "passive"))
    )
    (net (code "10") (name "Net-(D1-C)") (class "Default")
      (node (ref "D1") (pin "K") (pinfunction "C_K") (pintype "passive"))
      (node (ref "Q1") (pin "E") (pinfunction "E_E") (pintype "passive"))
    )
    (net (code "11") (name "Net-(D2-C)") (class "Default")
      (node (ref "C22") (pin "2") (pinfunction "2_2") (pintype "passive"))
      (node (ref "C27") (pin "1") (pinfunction "1_1") (pintype "passive"))
      (node (ref "C28") (pin "1") (pinfunction "1_1") (pintype "passive"))
      (node (ref "C32") (pin "-") (pinfunction "-_-") (pintype "passive"))
      (node (ref "C33") (pin "-") (pinfunction "-_-") (pintype "passive"))
      (node (ref "D10") (pin "A") (pinfunction "A_A") (pintype "passive"))
      (node (ref "D18") (pin "A") (pinfunction "A_A") (pintype "passive"))
      (node (ref "D19") (pin "A") (pinfunction "A_A") (pintype "passive"))
      (node (ref "D2") (pin "K") (pinfunction "C_K") (pintype "passive"))
      (node (ref "Q5") (pin "2") (pinfunction "C_2") (pintype "passive"))
      (node (ref "Q7") (pin "C") (pinfunction "C_C") (pintype "passive"))
      (node (ref "R15") (pin "2") (pinfunction "2_2") (pintype "passive"))
      (node (ref "R4") (pin "2") (pinfunction "2_2") (pintype "passive"))
    )
    (net (code "12") (name "Net-(D2-PadA)") (class "Default")
      (node (ref "D2") (pin "A") (pinfunction "A_A") (pintype "passive"))
      (node (ref "Q2") (pin "E") (pinfunction "E_E") (pintype "passive"))
    )
    (net (code "13") (name "Net-(D5-OUT)") (class "Default")
      (node (ref "D5") (pin "6") (pinfunction "OUT_6") (pintype "passive"))
      (node (ref "Q8") (pin "2") (pinfunction "G_2") (pintype "passive"))
      (node (ref "R11") (pin "1") (pinfunction "1_1") (pintype "passive"))
      (node (ref "R20") (pin "2") (pinfunction "2_2") (pintype "passive"))
    )
    (net (code "14") (name "Net-(D7-GND)") (class "Default")
      (node (ref "D7") (pin "4") (pinfunction "GND_4") (pintype "passive"))
      (node (ref "Q12") (pin "1") (pinfunction "D_1") (pintype "passive"))
      (node (ref "R21") (pin "2") (pinfunction "2_2") (pintype "passive"))
    )
    (net (code "15") (name "Net-(D8-C)") (class "Default")
      (node (ref "D8") (pin "K") (pinfunction "C_K") (pintype "passive"))
      (node (ref "Q13") (pin "B") (pinfunction "B_B") (pintype "passive"))
      (node (ref "R15") (pin "1") (pinfunction "1_1") (pintype "passive"))
    )
    (net (code "16") (name "Net-(D9-PadA)") (class "Default")
      (node (ref "D9") (pin "A") (pinfunction "A_A") (pintype "passive"))
      (node (ref "Q14") (pin "B") (pinfunction "B_B") (pintype "passive"))
      (node (ref "R16") (pin "2") (pinfunction "2_2") (pintype "passive"))
    )
    (net (code "17") (name "Net-(D15-C)") (class "Default")
      (node (ref "D15") (pin "K") (pinfunction "C_K") (pintype "passive"))
      (node (ref "R14") (pin "2") (pinfunction "2_2") (pintype "passive"))
      (node (ref "X5") (pin "2") (pinfunction "KL_2") (pintype "passive"))
    )
    (net (code "18") (name "Net-(IC1-+IN)") (class "Default")
      (node (ref "C12") (pin "2") (pinfunction "2_2") (pintype "passive"))
      (node (ref "C9") (pin "+") (pinfunction "+_+") (pintype "passive"))
      (node (ref "D13") (pin "C") (pinfunction "C_C") (pintype "passive"))
      (node (ref "D14") (pin "A") (pinfunction "A_A") (pintype "passive"))
      (node (ref "IC1") (pin "3") (pinfunction "+IN_3") (pintype "input"))
      (node (ref "R20") (pin "1") (pinfunction "1_1") (pintype "passive"))
    )
    (net (code "19") (name "Net-(IC1--IN)") (class "Default")
      (node (ref "C16") (pin "-") (pinfunction "-_-") (pintype "passive"))
      (node (ref "C5") (pin "1") (pinfunction "1_1") (pintype "passive"))
      (node (ref "D13") (pin "A") (pinfunction "A_A") (pintype "passive"))
      (node (ref "D14") (pin "C") (pinfunction "C_C") (pintype "passive"))
      (node (ref "IC1") (pin "2") (pinfunction "-IN_2") (pintype "input"))
      (node (ref "R7") (pin "2") (pinfunction "2_2") (pintype "passive"))
      (node (ref "R8") (pin "1") (pinfunction "1_1") (pintype "passive"))
    )
    (net (code "20") (name "Net-(IC1-OUT)") (class "Default")
      (node (ref "C5") (pin "2") (pinfunction "2_2") (pintype "passive"))
      (node (ref "C5") (pin "3") (pinfunction "2_3") (pintype "passive"))
      (node (ref "IC1") (pin "6") (pinfunction "OUT_6") (pintype "output"))
      (node (ref "R19") (pin "1") (pinfunction "1_1") (pintype "passive"))
    )
    (net (code "21") (name "Net-(IC2-+IN)") (class "Default")
      (node (ref "C15") (pin "2") (pinfunction "2_2") (pintype "passive"))
      (node (ref "C8") (pin "-") (pinfunction "-_-") (pintype "passive"))
      (node (ref "D12") (pin "C") (pinfunction "C_C") (pintype "passive"))
      (node (ref "D3") (pin "A") (pinfunction "A_A") (pintype "passive"))
      (node (ref "IC2") (pin "3") (pinfunction "+IN_3") (pintype "input"))
      (node (ref "R21") (pin "1") (pinfunction "1_1") (pintype "passive"))
    )
    (net (code "22") (name "Net-(IC2--IN)") (class "Default")
      (node (ref "C3") (pin "+") (pinfunction "+_+") (pintype "passive"))
      (node (ref "C4") (pin "1") (pinfunction "1_1") (pintype "passive"))
      (node (ref "D12") (pin "A") (pinfunction "A_A") (pintype "passive"))
      (node (ref "D3") (pin "C") (pinfunction "C_C") (pintype "passive"))
      (node (ref "IC2") (pin "2") (pinfunction "-IN_2") (pintype "input"))
      (node (ref "R10") (pin "1") (pinfunction "1_1") (pintype "passive"))
      (node (ref "R9") (pin "2") (pinfunction "2_2") (pintype "passive"))
    )
    (net (code "23") (name "Net-(IC2-OUT)") (class "Default")
      (node (ref "C4") (pin "2") (pinfunction "2_2") (pintype "passive"))
      (node (ref "C4") (pin "3") (pinfunction "2_3") (pintype "passive"))
      (node (ref "IC2") (pin "6") (pinfunction "OUT_6") (pintype "output"))
      (node (ref "R22") (pin "1") (pinfunction "1_1") (pintype "passive"))
    )
    (net (code "24") (name "Net-(Q1-PadB)") (class "Default")
      (node (ref "Q1") (pin "B") (pinfunction "B_B") (pintype "passive"))
      (node (ref "Q1") (pin "C") (pinfunction "C_C") (pintype "passive"))
      (node (ref "Q14") (pin "C") (pinfunction "C_C") (pintype "passive"))
      (node (ref "Q3") (pin "B") (pinfunction "B_B") (pintype "passive"))
    )
    (net (code "25") (name "Net-(Q3-PadE)") (class "Default")
      (node (ref "Q3") (pin "E") (pinfunction "E_E") (pintype "passive"))
      (node (ref "R1") (pin "2") (pinfunction "2_2") (pintype "passive"))
    )
    (net (code "26") (name "Net-(Q5-B)") (class "Default")
      (node (ref "C13") (pin "-") (pinfunction "-_-") (pintype "passive"))
      (node (ref "C14") (pin "2") (pinfunction "2_2") (pintype "passive"))
      (node (ref "D6") (pin "A") (pinfunction "A_A") (pintype "passive"))
      (node (ref "Q10\\") (pin "C") (pinfunction "C_C") (pintype "passive"))
      (node (ref "Q5") (pin "1") (pinfunction "B_1") (pintype "passive"))
    )
    (net (code "27") (name "Net-(Q5-E)") (class "Default")
      (node (ref "Q5") (pin "3") (pinfunction "E_3") (pintype "passive"))
      (node (ref "Q7") (pin "B") (pinfunction "B_B") (pintype "passive"))
    )
    (net (code "28") (name "Net-(Q6-PadB)") (class "Default")
      (node (ref "Q6") (pin "B") (pinfunction "B_B") (pintype "passive"))
      (node (ref "R19") (pin "2") (pinfunction "2_2") (pintype "passive"))
    )
    (net (code "29") (name "Net-(Q6-PadE)") (class "Default")
      (node (ref "Q6") (pin "E") (pinfunction "E_E") (pintype "passive"))
      (node (ref "R3") (pin "2") (pinfunction "2_2") (pintype "passive"))
    )
    (net (code "30") (name "Net-(Q8-S)") (class "Default")
      (node (ref "Q8") (pin "3") (pinfunction "S_3") (pintype "passive"))
      (node (ref "R11") (pin "2") (pinfunction "2_2") (pintype "passive"))
    )
    (net (code "31") (name "Net-(Q9-B)") (class "Default")
      (node (ref "C11") (pin "1") (pinfunction "1_1") (pintype "passive"))
      (node (ref "C7") (pin "+") (pinfunction "+_+") (pintype "passive"))
      (node (ref "D4") (pin "C") (pinfunction "C_C") (pintype "passive"))
      (node (ref "Q3") (pin "C") (pinfunction "C_C") (pintype "passive"))
      (node (ref "Q9") (pin "1") (pinfunction "B_1") (pintype "passive"))
    )
    (net (code "32") (name "Net-(Q9-C)") (class "Default")
      (node (ref "C23") (pin "1") (pinfunction "1_1") (pintype "passive"))
      (node (ref "C25") (pin "2") (pinfunction "2_2") (pintype "passive"))
      (node (ref "C26") (pin "2") (pinfunction "2_2") (pintype "passive"))
      (node (ref "C30") (pin "+") (pinfunction "+_+") (pintype "passive"))
      (node (ref "C31") (pin "+") (pinfunction "+_+") (pintype "passive"))
      (node (ref "D1") (pin "A") (pinfunction "A_A") (pintype "passive"))
      (node (ref "D11") (pin "C") (pinfunction "C_C") (pintype "passive"))
      (node (ref "D16") (pin "C") (pinfunction "C_C") (pintype "passive"))
      (node (ref "D17") (pin "C") (pinfunction "C_C") (pintype "passive"))
      (node (ref "Q4") (pin "C") (pinfunction "C_C") (pintype "passive"))
      (node (ref "Q9") (pin "2") (pinfunction "C_2") (pintype "passive"))
      (node (ref "R1") (pin "1") (pinfunction "1_1") (pintype "passive"))
      (node (ref "R16") (pin "1") (pinfunction "1_1") (pintype "passive"))
    )
    (net (code "33") (name "Net-(Q9-E)") (class "Default")
      (node (ref "Q4") (pin "B") (pinfunction "B_B") (pintype "passive"))
      (node (ref "Q9") (pin "3") (pinfunction "E_3") (pintype "passive"))
    )
    (net (code "34") (name "Net-(Q10\\-PadB)") (class "Default")
      (node (ref "Q10\\") (pin "B") (pinfunction "B_B") (pintype "passive"))
      (node (ref "Q13") (pin "C") (pinfunction "C_C") (pintype "passive"))
      (node (ref "Q2") (pin "B") (pinfunction "B_B") (pintype "passive"))
      (node (ref "Q2") (pin "C") (pinfunction "C_C") (pintype "passive"))
    )
    (net (code "35") (name "Net-(Q10\\-PadE)") (class "Default")
      (node (ref "Q10\\") (pin "E") (pinfunction "E_E") (pintype "passive"))
      (node (ref "R4") (pin "1") (pinfunction "1_1") (pintype "passive"))
    )
    (net (code "36") (name "Net-(Q11-PadB)") (class "Default")
      (node (ref "Q11") (pin "B") (pinfunction "B_B") (pintype "passive"))
      (node (ref "R22") (pin "2") (pinfunction "2_2") (pintype "passive"))
    )
    (net (code "37") (name "Net-(Q11-PadE)") (class "Default")
      (node (ref "Q11") (pin "E") (pinfunction "E_E") (pintype "passive"))
      (node (ref "R6") (pin "1") (pinfunction "1_1") (pintype "passive"))
    )
    (net (code "38") (name "Net-(Q12-S)") (class "Default")
      (node (ref "Q12") (pin "3") (pinfunction "S_3") (pintype "passive"))
      (node (ref "R12") (pin "2") (pinfunction "2_2") (pintype "passive"))
    )
    (net (code "39") (name "Net-(Q13-PadE)") (class "Default")
      (node (ref "Q13") (pin "E") (pinfunction "E_E") (pintype "passive"))
      (node (ref "R5") (pin "2") (pinfunction "2_2") (pintype "passive"))
    )
    (net (code "40") (name "Net-(Q14-PadE)") (class "Default")
      (node (ref "Q14") (pin "E") (pinfunction "E_E") (pintype "passive"))
      (node (ref "R2") (pin "1") (pinfunction "1_1") (pintype "passive"))
    )
    (net (code "41") (name "Net-(U$1-EN)") (class "Default")
      (node (ref "B1") (pin "+") (pinfunction "+_+") (pintype "passive"))
      (node (ref "C2") (pin "1") (pinfunction "1_1") (pintype "passive"))
      (node (ref "C35") (pin "+") (pinfunction "+_+") (pintype "passive"))
      (node (ref "C36") (pin "1") (pinfunction "1_1") (pintype "passive"))
      (node (ref "C39") (pin "+") (pinfunction "+_+") (pintype "passive"))
      (node (ref "U$1") (pin "1") (pinfunction "IN_1") (pintype "bidirectional"))
      (node (ref "U$1") (pin "2") (pinfunction "IN_2") (pintype "bidirectional"))
      (node (ref "U$1") (pin "3") (pinfunction "IN_3") (pintype "bidirectional"))
      (node (ref "U$1") (pin "4") (pinfunction "EN_4") (pintype "bidirectional"))
      (node (ref "U$1") (pin "7") (pinfunction "PGFB_7") (pintype "bidirectional"))
    )
    (net (code "42") (name "Net-(U$1-ILIM)") (class "Default")
      (node (ref "R18") (pin "2") (pinfunction "2_2") (pintype "passive"))
      (node (ref "U$1") (pin "6") (pinfunction "ILIM_6") (pintype "bidirectional"))
    )
    (net (code "43") (name "Net-(U$1-OUTS)") (class "Default")
      (node (ref "U$1") (pin "10") (pinfunction "OUTS_10") (pintype "bidirectional"))
      (node (ref "U$2") (pin "3") (pinfunction "1_3") (pintype "passive"))
    )
    (net (code "44") (name "Net-(U$1-SET)") (class "Default")
      (node (ref "C1") (pin "1") (pinfunction "1_1") (pintype "passive"))
      (node (ref "R17") (pin "2") (pinfunction "2_2") (pintype "passive"))
      (node (ref "U$1") (pin "8") (pinfunction "SET_8") (pintype "bidirectional"))
    )
    (net (code "45") (name "Net-(U$2B-1)") (class "Default")
      (node (ref "C29") (pin "1") (pinfunction "1_1") (pintype "passive"))
      (node (ref "C34") (pin "+") (pinfunction "+_+") (pintype "passive"))
      (node (ref "C37") (pin "1") (pinfunction "1_1") (pintype "passive"))
      (node (ref "C42") (pin "+") (pinfunction "+_+") (pintype "passive"))
      (node (ref "JP1") (pin "2") (pinfunction "2_2") (pintype "passive"))
      (node (ref "U$1") (pin "11") (pinfunction "OUT_11") (pintype "bidirectional"))
      (node (ref "U$1") (pin "12") (pinfunction "OUT_12") (pintype "bidirectional"))
      (node (ref "U$2") (pin "4") (pinfunction "1_4") (pintype "passive"))
      (node (ref "X9") (pin "2") (pinfunction "KL_2") (pintype "passive"))
    )
    (net (code "46") (name "Net-(U$2B-2)") (class "Default")
      (node (ref "C1") (pin "2") (pinfunction "2_2") (pintype "passive"))
      (node (ref "R17") (pin "1") (pinfunction "1_1") (pintype "passive"))
      (node (ref "U$2") (pin "6") (pinfunction "2_6") (pintype "passive"))
    )
    (net (code "47") (name "Net-(U$5-EN)") (class "Default")
      (node (ref "B3") (pin "+") (pinfunction "+_+") (pintype "passive"))
      (node (ref "C38") (pin "+") (pinfunction "+_+") (pintype "passive"))
      (node (ref "C45") (pin "+") (pinfunction "+_+") (pintype "passive"))
      (node (ref "C47") (pin "1") (pinfunction "1_1") (pintype "passive"))
      (node (ref "C50") (pin "1") (pinfunction "1_1") (pintype "passive"))
      (node (ref "U$5") (pin "1") (pinfunction "IN_1") (pintype "bidirectional"))
      (node (ref "U$5") (pin "2") (pinfunction "IN_2") (pintype "bidirectional"))
      (node (ref "U$5") (pin "3") (pinfunction "IN_3") (pintype "bidirectional"))
      (node (ref "U$5") (pin "4") (pinfunction "EN_4") (pintype "bidirectional"))
      (node (ref "U$5") (pin "7") (pinfunction "PGFB_7") (pintype "bidirectional"))
    )
    (net (code "48") (name "Net-(U$5-ILIM)") (class "Default")
      (node (ref "R26") (pin "2") (pinfunction "2_2") (pintype "passive"))
      (node (ref "U$5") (pin "6") (pinfunction "ILIM_6") (pintype "bidirectional"))
    )
    (net (code "49") (name "Net-(U$5-OUTS)") (class "Default")
      (node (ref "U$5") (pin "10") (pinfunction "OUTS_10") (pintype "bidirectional"))
      (node (ref "U$6") (pin "3") (pinfunction "1_3") (pintype "passive"))
    )
    (net (code "50") (name "Net-(U$5-SET)") (class "Default")
      (node (ref "C46") (pin "1") (pinfunction "1_1") (pintype "passive"))
      (node (ref "R25") (pin "2") (pinfunction "2_2") (pintype "passive"))
      (node (ref "U$5") (pin "8") (pinfunction "SET_8") (pintype "bidirectional"))
    )
    (net (code "51") (name "Net-(U$6B-2)") (class "Default")
      (node (ref "C46") (pin "2") (pinfunction "2_2") (pintype "passive"))
      (node (ref "R25") (pin "1") (pinfunction "1_1") (pintype "passive"))
      (node (ref "U$6") (pin "6") (pinfunction "2_6") (pintype "passive"))
    )
    (net (code "52") (name "Net-(U$9-EN)") (class "Default")
      (node (ref "B5") (pin "+") (pinfunction "+_+") (pintype "passive"))
      (node (ref "C40") (pin "+") (pinfunction "+_+") (pintype "passive"))
      (node (ref "C59") (pin "+") (pinfunction "+_+") (pintype "passive"))
      (node (ref "C61") (pin "1") (pinfunction "1_1") (pintype "passive"))
      (node (ref "C64") (pin "1") (pinfunction "1_1") (pintype "passive"))
      (node (ref "U$9") (pin "1") (pinfunction "IN_1") (pintype "bidirectional"))
      (node (ref "U$9") (pin "2") (pinfunction "IN_2") (pintype "bidirectional"))
      (node (ref "U$9") (pin "3") (pinfunction "IN_3") (pintype "bidirectional"))
      (node (ref "U$9") (pin "4") (pinfunction "EN_4") (pintype "bidirectional"))
      (node (ref "U$9") (pin "7") (pinfunction "PGFB_7") (pintype "bidirectional"))
    )
    (net (code "53") (name "Net-(U$9-ILIM)") (class "Default")
      (node (ref "R30") (pin "2") (pinfunction "2_2") (pintype "passive"))
      (node (ref "U$9") (pin "6") (pinfunction "ILIM_6") (pintype "bidirectional"))
    )
    (net (code "54") (name "Net-(U$9-SET)") (class "Default")
      (node (ref "C60") (pin "1") (pinfunction "1_1") (pintype "passive"))
      (node (ref "R29") (pin "2") (pinfunction "2_2") (pintype "passive"))
      (node (ref "U$9") (pin "8") (pinfunction "SET_8") (pintype "bidirectional"))
    )
    (net (code "55") (name "Net-(U$10A-1)") (class "Default")
      (node (ref "U$10") (pin "3") (pinfunction "1_3") (pintype "passive"))
      (node (ref "U$9") (pin "10") (pinfunction "OUTS_10") (pintype "bidirectional"))
    )
    (net (code "56") (name "Net-(U$10B-2)") (class "Default")
      (node (ref "C60") (pin "2") (pinfunction "2_2") (pintype "passive"))
      (node (ref "R29") (pin "1") (pinfunction "1_1") (pintype "passive"))
      (node (ref "U$10") (pin "6") (pinfunction "2_6") (pintype "passive"))
    )
    (net (code "57") (name "Net-(X5A-KL)") (class "Default")
      (node (ref "D15") (pin "A") (pinfunction "A_A") (pintype "passive"))
      (node (ref "R13") (pin "1") (pinfunction "1_1") (pintype "passive"))
      (node (ref "X5") (pin "1") (pinfunction "KL_1") (pintype "passive"))
    )
    (net (code "58") (name "Net-(X6B-KL)") (class "Default")
      (node (ref "C26") (pin "1") (pinfunction "1_1") (pintype "passive"))
      (node (ref "C28") (pin "2") (pinfunction "2_2") (pintype "passive"))
      (node (ref "D17") (pin "A") (pinfunction "A_A") (pintype "passive"))
      (node (ref "D19") (pin "C") (pinfunction "C_C") (pintype "passive"))
      (node (ref "X6") (pin "2") (pinfunction "KL_2") (pintype "passive"))
    )
    (net (code "59") (name "Net-(X7A-KL)") (class "Default")
      (node (ref "C25") (pin "1") (pinfunction "1_1") (pintype "passive"))
      (node (ref "C27") (pin "2") (pinfunction "2_2") (pintype "passive"))
      (node (ref "D16") (pin "A") (pinfunction "A_A") (pintype "passive"))
      (node (ref "D18") (pin "C") (pinfunction "C_C") (pintype "passive"))
      (node (ref "X7") (pin "1") (pinfunction "KL_1") (pintype "passive"))
    )
    (net (code "60") (name "Net-(X8A-KL)") (class "Default")
      (node (ref "B1") (pin "AC2") (pinfunction "AC2_AC2") (pintype "passive"))
      (node (ref "X8") (pin "1") (pinfunction "KL_1") (pintype "passive"))
    )
    (net (code "61") (name "Net-(X8B-KL)") (class "Default")
      (node (ref "B1") (pin "AC1") (pinfunction "AC1_AC1") (pintype "passive"))
      (node (ref "X8") (pin "2") (pinfunction "KL_2") (pintype "passive"))
    )
    (net (code "62") (name "Net-(X12A-KL)") (class "Default")
      (node (ref "B3") (pin "AC2") (pinfunction "AC2_AC2") (pintype "passive"))
      (node (ref "X12") (pin "1") (pinfunction "KL_1") (pintype "passive"))
    )
    (net (code "63") (name "Net-(X12B-KL)") (class "Default")
      (node (ref "B3") (pin "AC1") (pinfunction "AC1_AC1") (pintype "passive"))
      (node (ref "X12") (pin "2") (pinfunction "KL_2") (pintype "passive"))
    )
    (net (code "64") (name "Net-(X16A-KL)") (class "Default")
      (node (ref "B5") (pin "AC2") (pinfunction "AC2_AC2") (pintype "passive"))
      (node (ref "X16") (pin "1") (pinfunction "KL_1") (pintype "passive"))
    )
    (net (code "65") (name "Net-(X16B-KL)") (class "Default")
      (node (ref "B5") (pin "AC1") (pinfunction "AC1_AC1") (pintype "passive"))
      (node (ref "X16") (pin "2") (pinfunction "KL_2") (pintype "passive"))
    )
    (net (code "66") (name "V+") (class "Default")
      (node (ref "C16") (pin "+") (pinfunction "+_+") (pintype "passive"))
      (node (ref "C18") (pin "2") (pinfunction "2_2") (pintype "passive"))
      (node (ref "C20") (pin "2") (pinfunction "2_2") (pintype "passive"))
      (node (ref "C24") (pin "1") (pinfunction "1_1") (pintype "passive"))
      (node (ref "C6") (pin "+") (pinfunction "+_+") (pintype "passive"))
      (node (ref "D11") (pin "A") (pinfunction "A_A") (pintype "passive"))
      (node (ref "IC1") (pin "7") (pinfunction "V+_7") (pintype "power_in"))
      (node (ref "Q4") (pin "E") (pinfunction "E_E") (pintype "passive"))
      (node (ref "Q8") (pin "1") (pinfunction "D_1") (pintype "passive"))
      (node (ref "R13") (pin "2") (pinfunction "2_2") (pintype "passive"))
      (node (ref "R8") (pin "2") (pinfunction "2_2") (pintype "passive"))
      (node (ref "X1") (pin "1") (pinfunction "KL_1") (pintype "passive"))
      (node (ref "X2") (pin "1") (pinfunction "KL_1") (pintype "passive"))
      (node (ref "X3") (pin "1") (pinfunction "KL_1") (pintype "passive"))
      (node (ref "X4") (pin "1") (pinfunction "KL_1") (pintype "passive"))
    )
    (net (code "67") (name "V-") (class "Default")
      (node (ref "C10") (pin "-") (pinfunction "-_-") (pintype "passive"))
      (node (ref "C17") (pin "1") (pinfunction "1_1") (pintype "passive"))
      (node (ref "C19") (pin "1") (pinfunction "1_1") (pintype "passive"))
      (node (ref "C21") (pin "2") (pinfunction "2_2") (pintype "passive"))
      (node (ref "C3") (pin "-") (pinfunction "-_-") (pintype "passive"))
      (node (ref "D10") (pin "C") (pinfunction "C_C") (pintype "passive"))
      (node (ref "IC2") (pin "4") (pinfunction "V-_4") (pintype "power_in"))
      (node (ref "Q12") (pin "2") (pinfunction "G_2") (pintype "passive"))
      (node (ref "Q7") (pin "E") (pinfunction "E_E") (pintype "passive"))
      (node (ref "R12") (pin "1") (pinfunction "1_1") (pintype "passive"))
      (node (ref "R14") (pin "1") (pinfunction "1_1") (pintype "passive"))
      (node (ref "R9") (pin "1") (pinfunction "1_1") (pintype "passive"))
      (node (ref "X1") (pin "3") (pinfunction "KL_3") (pintype "passive"))
      (node (ref "X2") (pin "3") (pinfunction "KL_3") (pintype "passive"))
      (node (ref "X3") (pin "3") (pinfunction "KL_3") (pintype "passive"))
      (node (ref "X4") (pin "3") (pinfunction "KL_3") (pintype "passive"))
    )
    (net (code "68") (name "unconnected-(IC1-TRIM1-Pad1)") (class "Default")
      (node (ref "IC1") (pin "1") (pinfunction "TRIM1_1") (pintype "passive"))
    )
    (net (code "69") (name "unconnected-(IC1-TRIM2-Pad8)") (class "Default")
      (node (ref "IC1") (pin "8") (pinfunction "TRIM2_8") (pintype "passive"))
    )
    (net (code "70") (name "unconnected-(IC2-TRIM1-Pad1)") (class "Default")
      (node (ref "IC2") (pin "1") (pinfunction "TRIM1_1") (pintype "passive"))
    )
    (net (code "71") (name "unconnected-(IC2-TRIM2-Pad8)") (class "Default")
      (node (ref "IC2") (pin "8") (pinfunction "TRIM2_8") (pintype "passive"))
    )
    (net (code "72") (name "unconnected-(U$1-PG-Pad5)") (class "Default")
      (node (ref "U$1") (pin "5") (pinfunction "PG_5") (pintype "bidirectional"))
    )
    (net (code "73") (name "unconnected-(U$5-PG-Pad5)") (class "Default")
      (node (ref "U$5") (pin "5") (pinfunction "PG_5") (pintype "bidirectional"))
    )
    (net (code "74") (name "unconnected-(U$9-PG-Pad5)") (class "Default")
      (node (ref "U$9") (pin "5") (pinfunction "PG_5") (pintype "bidirectional"))
    )
  )
)
